# GND_Loop.net
KiCad netlist of a schematic drawn in Altium Designer
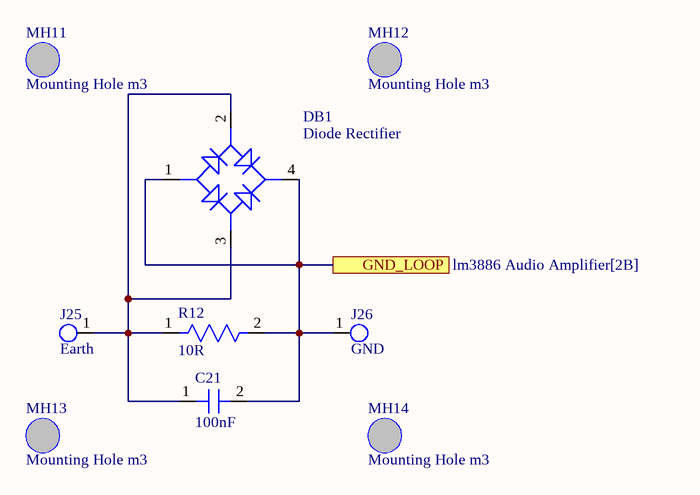
[diagram p0: GND Loop.SchDoc]

(export (version "E")
  (design (tool "Eeschema 10.0.6"))
  (components
    (comp (ref "C21")
      (value "100nF")
      (footprint "Capacitor P15 7.2x18.3mm")
      (libsource (lib "lm3886 Schlib") (part "Capacitor"))
    )
    (comp (ref "DB1")
      (value "Diode Rectifier")
      (footprint "KBPC rectifier")
      (libsource (lib "lm3886 Schlib") (part "Diode Rectifier"))
    )
    (comp (ref "J25")
      (value "Earth")
      (footprint "Terminal 6.3mm male")
      (libsource (lib "lm3886 Schlib") (part "6.3mm Male Terminal"))
    )
    (comp (ref "J26")
      (value "GND")
      (footprint "Terminal 6.3mm male")
      (libsource (lib "lm3886 Schlib") (part "6.3mm Male Terminal"))
    )
    (comp (ref "MH11")
      (value "Mounting Hole m3")
      (footprint "Mounting Hole")
      (libsource (lib "lm3886 Schlib") (part "Mounting Hole m3"))
    )
    (comp (ref "MH12")
      (value "Mounting Hole m3")
      (footprint "Mounting Hole")
      (libsource (lib "lm3886 Schlib") (part "Mounting Hole m3"))
    )
    (comp (ref "MH13")
      (value "Mounting Hole m3")
      (footprint "Mounting Hole")
      (libsource (lib "lm3886 Schlib") (part "Mounting Hole m3"))
    )
    (comp (ref "MH14")
      (value "Mounting Hole m3")
      (footprint "Mounting Hole")
      (libsource (lib "lm3886 Schlib") (part "Mounting Hole m3"))
    )
    (comp (ref "R12")
      (value "10R")
      (footprint "Resistor 0823 5W")
      (libsource (lib "lm3886 Schlib") (part "Resistor"))
    )
  )
  (nets
    (net (code "1") (name "/GND_LOOP") (class "Default")
      (node (ref "C21") (pin "2") (pintype "passive"))
      (node (ref "DB1") (pin "1") (pintype "passive"))
      (node (ref "DB1") (pin "4") (pintype "passive"))
      (node (ref "J26") (pin "1") (pintype "passive"))
      (node (ref "R12") (pin "2") (pintype "passive"))
    )
    (net (code "2") (name "Net-(C21-Pad1)") (class "Default")
      (node (ref "C21") (pin "1") (pintype "passive"))
      (node (ref "DB1") (pin "2") (pintype "passive"))
      (node (ref "DB1") (pin "3") (pintype "passive"))
      (node (ref "J25") (pin "1") (pintype "passive"))
      (node (ref "R12") (pin "1") (pintype "passive"))
    )
  )
)
